# 2_EE-10_and_SIM_AFE_Interface.net
KiCad netlist of a schematic drawn in Altium Designer
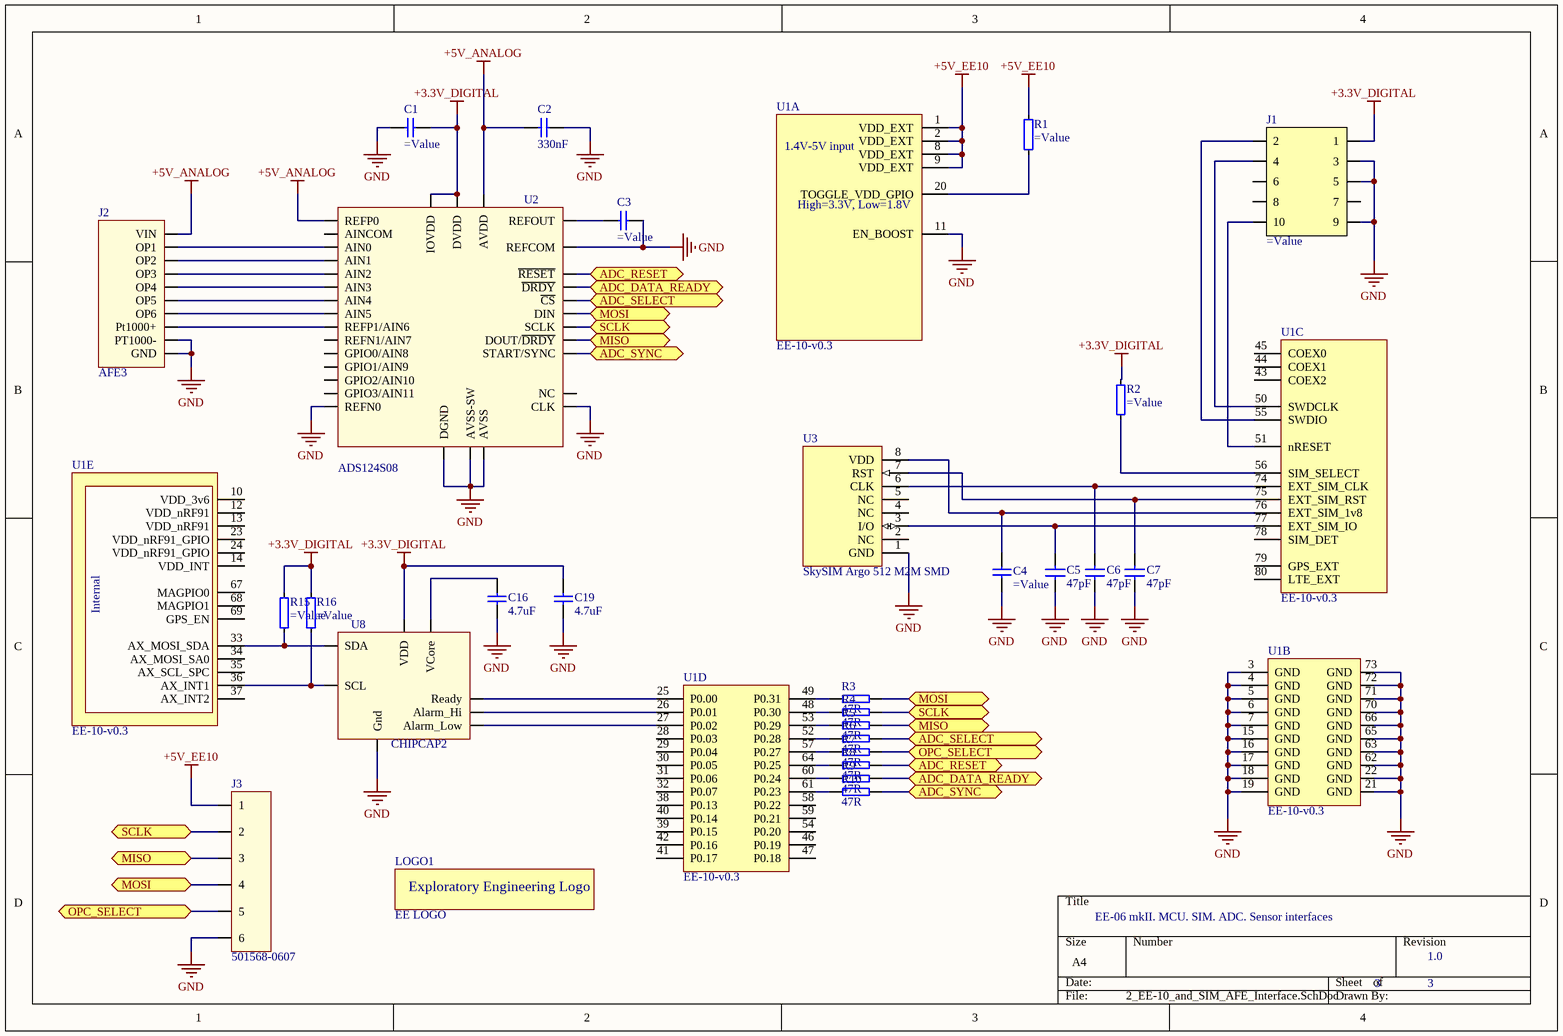
[diagram p0: 2_EE-10_and_SIM_AFE_Interface.SchDoc]

(export (version "E")
  (design (tool "Eeschema 10.0.6"))
  (components
    (comp (ref "C1")
      (value "~")
      (footprint "CAPC1005X04L")
      (description "CAP CER 100nF 16V X7R 0402")
      (fields
        (field (name "MANUFACTURER") "Murata Electronics North America")
        (field (name "MANUFACTURER PART NUMBER") "GRM155R71C104KA88D")
      )
      (libsource (lib "Skunkworks Library") (part "GRM155R71C104KA88D"))
    )
    (comp (ref "C2")
      (value "330nF")
      (footprint "CAPC1005X04L")
      (description "CAP CER 0.33UF 10V X5R 0402")
      (fields
        (field (name "MANUFACTURER") "Yageo")
        (field (name "MANUFACTURER PART NUMBER") "CC0402KRX5R6BB334")
      )
      (libsource (lib "Skunkworks Library") (part "CC0402KRX5R6BB334"))
    )
    (comp (ref "C3")
      (value "~")
      (footprint "CAPC1005X04L")
      (description "CAP CER 1UF 6.3V X7R 0402")
      (fields
        (field (name "MANUFACTURER") "Murata Electronics North America")
        (field (name "MANUFACTURER PART NUMBER") "GRM155R70J105KA12D")
      )
      (libsource (lib "Skunkworks Library") (part "GRM155R70J105KA12D"))
    )
    (comp (ref "C4")
      (value "~")
      (footprint "CAPC1005X04L")
      (description "CAP CER 100nF 16V X7R 0402")
      (fields
        (field (name "MANUFACTURER") "Murata Electronics North America")
        (field (name "MANUFACTURER PART NUMBER") "GRM155R71C104KA88D")
      )
      (libsource (lib "Skunkworks Library") (part "GRM155R71C104KA88D"))
    )
    (comp (ref "C5")
      (value "47pF")
      (footprint "CAPC1005X04L")
      (description "Multilayer Ceramic Capacitors MLCC - SMD/SMT 0402 47pF 50volts C0G 1%")
      (libsource (lib "Skunkworks Library") (part "GRM1555C1H470FA01D"))
    )
    (comp (ref "C6")
      (value "47pF")
      (footprint "CAPC1005X04L")
      (description "Multilayer Ceramic Capacitors MLCC - SMD/SMT 0402 47pF 50volts C0G 1%")
      (libsource (lib "Skunkworks Library") (part "GRM1555C1H470FA01D"))
    )
    (comp (ref "C7")
      (value "47pF")
      (footprint "CAPC1005X04L")
      (description "Multilayer Ceramic Capacitors MLCC - SMD/SMT 0402 47pF 50volts C0G 1%")
      (libsource (lib "Skunkworks Library") (part "GRM1555C1H470FA01D"))
    )
    (comp (ref "C16")
      (value "4.7uF")
      (footprint "CAPC1005X04L")
      (description "CAP CER 4.7UF 6.3V X5R 0402")
      (fields
        (field (name "MANUFACTURER") "Murata")
        (field (name "MANUFACTURER PART NUMBER") "GRM155R60J475ME47D")
      )
      (libsource (lib "Skunkworks Library") (part "GRM155R60J475ME47D"))
    )
    (comp (ref "C19")
      (value "4.7uF")
      (footprint "CAPC1005X04L")
      (description "CAP CER 4.7UF 6.3V X5R 0402")
      (fields
        (field (name "MANUFACTURER") "Murata")
        (field (name "MANUFACTURER PART NUMBER") "GRM155R60J475ME47D")
      )
      (libsource (lib "Skunkworks Library") (part "GRM155R60J475ME47D"))
    )
    (comp (ref "J1")
      (value "~")
      (footprint "FTSH-105-K")
      (description "CONN HEADER 10POS DUAL .05\" SMD")
      (fields
        (field (name "MANUFACTURER") "Samtec Inc.")
        (field (name "MANUFACTURER PART NUMBER") "FTSH-105-01-F-DV-K-P")
      )
      (libsource (lib "Skunkworks Library") (part "FTSH-105-01-F-DV-K-P"))
    )
    (comp (ref "J2")
      (value "AFE3")
      (footprint "AFE3_IDC_CABLE")
      (libsource (lib "Skunkworks Library") (part "AFE3"))
    )
    (comp (ref "J3")
      (value "501568-0607")
      (footprint "CONN 6 PIN PICOCLASP")
      (description "CONN HEADER SMD R/A 6POS 1MM")
      (fields (field (name "MANUFACTURER") "Molex"))
      (libsource (lib "Skunkworks Library") (part "501568-0607"))
    )
    (comp (ref "LOGO1")
      (value "EE LOGO")
      (footprint "EE_LOGO")
      (description "Exploratory Engineering Logo Silkscreen")
      (libsource (lib "Skunkworks Library") (part "EE-LOGO"))
    )
    (comp (ref "R1")
      (value "~")
      (footprint "RESC1005X04L")
      (description "RES SMD 10K OHM 1% 1/16W 0402")
      (fields
        (field (name "MANUFACTURER") "Yageo")
        (field (name "MANUFACTURER PART NUMBER") "RC0402FR-0710KL")
      )
      (libsource (lib "Skunkworks Library") (part "RC0402FR-0710KL"))
    )
    (comp (ref "R2")
      (value "~")
      (footprint "RESC1005X04L")
      (description "RES SMD 10K OHM 1% 1/16W 0402")
      (fields
        (field (name "MANUFACTURER") "Yageo")
        (field (name "MANUFACTURER PART NUMBER") "RC0402FR-0710KL")
      )
      (libsource (lib "Skunkworks Library") (part "RC0402FR-0710KL"))
    )
    (comp (ref "R3")
      (value "47R")
      (footprint "RESC1005X04L")
      (description "RES SMD 47 OHM 5% 1/16W 0402")
      (fields
        (field (name "MANUFACTURER") "Yageo")
        (field (name "MANUFACTURER PART NUMBER") "RC0402JR-0747RL")
      )
      (libsource (lib "Skunkworks Library") (part "RC0402JR-0747RL"))
    )
    (comp (ref "R4")
      (value "47R")
      (footprint "RESC1005X04L")
      (description "RES SMD 47 OHM 5% 1/16W 0402")
      (fields
        (field (name "MANUFACTURER") "Yageo")
        (field (name "MANUFACTURER PART NUMBER") "RC0402JR-0747RL")
      )
      (libsource (lib "Skunkworks Library") (part "RC0402JR-0747RL"))
    )
    (comp (ref "R5")
      (value "47R")
      (footprint "RESC1005X04L")
      (description "RES SMD 47 OHM 5% 1/16W 0402")
      (fields
        (field (name "MANUFACTURER") "Yageo")
        (field (name "MANUFACTURER PART NUMBER") "RC0402JR-0747RL")
      )
      (libsource (lib "Skunkworks Library") (part "RC0402JR-0747RL"))
    )
    (comp (ref "R6")
      (value "47R")
      (footprint "RESC1005X04L")
      (description "RES SMD 47 OHM 5% 1/16W 0402")
      (fields
        (field (name "MANUFACTURER") "Yageo")
        (field (name "MANUFACTURER PART NUMBER") "RC0402JR-0747RL")
      )
      (libsource (lib "Skunkworks Library") (part "RC0402JR-0747RL"))
    )
    (comp (ref "R7")
      (value "47R")
      (footprint "RESC1005X04L")
      (description "RES SMD 47 OHM 5% 1/16W 0402")
      (fields
        (field (name "MANUFACTURER") "Yageo")
        (field (name "MANUFACTURER PART NUMBER") "RC0402JR-0747RL")
      )
      (libsource (lib "Skunkworks Library") (part "RC0402JR-0747RL"))
    )
    (comp (ref "R8")
      (value "47R")
      (footprint "RESC1005X04L")
      (description "RES SMD 47 OHM 5% 1/16W 0402")
      (fields
        (field (name "MANUFACTURER") "Yageo")
        (field (name "MANUFACTURER PART NUMBER") "RC0402JR-0747RL")
      )
      (libsource (lib "Skunkworks Library") (part "RC0402JR-0747RL"))
    )
    (comp (ref "R9")
      (value "47R")
      (footprint "RESC1005X04L")
      (description "RES SMD 47 OHM 5% 1/16W 0402")
      (fields
        (field (name "MANUFACTURER") "Yageo")
        (field (name "MANUFACTURER PART NUMBER") "RC0402JR-0747RL")
      )
      (libsource (lib "Skunkworks Library") (part "RC0402JR-0747RL"))
    )
    (comp (ref "R10")
      (value "47R")
      (footprint "RESC1005X04L")
      (description "RES SMD 47 OHM 5% 1/16W 0402")
      (fields
        (field (name "MANUFACTURER") "Yageo")
        (field (name "MANUFACTURER PART NUMBER") "RC0402JR-0747RL")
      )
      (libsource (lib "Skunkworks Library") (part "RC0402JR-0747RL"))
    )
    (comp (ref "R15")
      (value "~")
      (footprint "RESC1005X04L")
      (description "RES SMD 10K OHM 1% 1/16W 0402")
      (fields
        (field (name "MANUFACTURER") "Yageo")
        (field (name "MANUFACTURER PART NUMBER") "RC0402FR-0710KL")
      )
      (libsource (lib "Skunkworks Library") (part "RC0402FR-0710KL"))
    )
    (comp (ref "R16")
      (value "~")
      (footprint "RESC1005X04L")
      (description "RES SMD 10K OHM 1% 1/16W 0402")
      (fields
        (field (name "MANUFACTURER") "Yageo")
        (field (name "MANUFACTURER PART NUMBER") "RC0402FR-0710KL")
      )
      (libsource (lib "Skunkworks Library") (part "RC0402FR-0710KL"))
    )
    (comp (ref "U1")
      (value "EE-10-v0.3")
      (footprint "EE-10_V0.3")
      (description "EE-10 v0.3 PCB Module")
      (fields (field (name "MANUFACTURER") "Telenor"))
      (libsource (lib "Skunkworks Library") (part "EE-10-v0.3"))
    )
    (comp (ref "U2")
      (value "ADS124S08")
      (footprint "PQFP-G32")
      (description "IC ADC 24BIT 8CH I2C 32-TQFP")
      (fields
        (field (name "MANUFACTURER") "Texas Instruments")
        (field (name "MANUFACTURER PART NUMBER") "ADS124S08IPBS")
      )
      (libsource (lib "Skunkworks Library") (part "ADS124S08IPBS"))
    )
    (comp (ref "U3")
      (value "SkySIM Argo 512 M2M SMD")
      (footprint "QFN127P500X600X90_HS-9N")
      (description "SkySIM® Argo 512 M2M SMD - LTE")
      (libsource (lib "Skunkworks Library") (part "SKYSIM-ARGO-LTE-MFF2"))
    )
    (comp (ref "U8")
      (value "CHIPCAP2")
      (footprint "SENSOR_CHIPCAP2")
      (description "SENSOR HUMI/TEMP 3.3V I2C 2% SMD")
      (fields (field (name "MANUFACTURER") "Amphenol") (field (name "MANUFACTURER PART NUMBER") "CC2A35"))
      (libsource (lib "Skunkworks Library") (part "CC2D23S"))
    )
  )
  (nets
    (net (code "1") (name "+3.3V_DIGITAL") (class "Default")
      (node (ref "C1") (pin "1") (pinfunction "1_1") (pintype "passive"))
      (node (ref "C19") (pin "2") (pinfunction "2_2") (pintype "passive"))
      (node (ref "J1") (pin "1") (pinfunction "1_1") (pintype "passive"))
      (node (ref "R15") (pin "2") (pinfunction "2_2") (pintype "passive"))
      (node (ref "R16") (pin "2") (pinfunction "2_2") (pintype "passive"))
      (node (ref "R2") (pin "2") (pinfunction "2_2") (pintype "passive"))
      (node (ref "U2") (pin "15") (pinfunction "IOVDD_15") (pintype "passive"))
      (node (ref "U2") (pin "16") (pinfunction "DVDD_16") (pintype "passive"))
      (node (ref "U8") (pin "3") (pinfunction "VDD_3") (pintype "passive"))
    )
    (net (code "2") (name "+5V_ANALOG") (class "Default")
      (node (ref "C2") (pin "1") (pinfunction "1_1") (pintype "passive"))
      (node (ref "J2") (pin "5") (pinfunction "VIN_5") (pintype "passive"))
      (node (ref "U2") (pin "26") (pinfunction "AVDD_26") (pintype "passive"))
      (node (ref "U2") (pin "30") (pinfunction "REFP0_30") (pintype "passive"))
    )
    (net (code "3") (name "+5V_EE10") (class "Default")
      (node (ref "J3") (pin "1") (pinfunction "1_1") (pintype "passive"))
      (node (ref "R1") (pin "2") (pinfunction "2_2") (pintype "passive"))
      (node (ref "U1") (pin "1") (pinfunction "VDD_EXT_1") (pintype "passive"))
      (node (ref "U1") (pin "2") (pinfunction "VDD_EXT_2") (pintype "passive"))
      (node (ref "U1") (pin "8") (pinfunction "VDD_EXT_8") (pintype "passive"))
      (node (ref "U1") (pin "9") (pinfunction "VDD_EXT_9") (pintype "passive"))
    )
    (net (code "4") (name "/ADC_DATA_READY") (class "Default")
      (node (ref "R9") (pin "2") (pintype "passive"))
      (node (ref "U2") (pin "13") (pinfunction "~{DRDY}_13") (pintype "passive"))
    )
    (net (code "5") (name "/ADC_RESET") (class "Default")
      (node (ref "R8") (pin "2") (pintype "passive"))
      (node (ref "U2") (pin "18") (pinfunction "~{RESET}_18") (pintype "passive"))
    )
    (net (code "6") (name "/ADC_SELECT") (class "Default")
      (node (ref "R6") (pin "2") (pintype "passive"))
      (node (ref "U2") (pin "9") (pinfunction "~{CS}_9") (pintype "passive"))
    )
    (net (code "7") (name "/ADC_SYNC") (class "Default")
      (node (ref "R10") (pin "2") (pintype "passive"))
      (node (ref "U2") (pin "8") (pinfunction "START/SYNC_8") (pintype "passive"))
    )
    (net (code "8") (name "/MISO") (class "Default")
      (node (ref "J3") (pin "3") (pinfunction "3_3") (pintype "passive"))
      (node (ref "R5") (pin "2") (pintype "passive"))
      (node (ref "U2") (pin "12") (pinfunction "DOUT/~{DRDY}_12") (pintype "passive"))
    )
    (net (code "9") (name "/MOSI") (class "Default")
      (node (ref "J3") (pin "4") (pinfunction "4_4") (pintype "passive"))
      (node (ref "R3") (pin "2") (pintype "passive"))
      (node (ref "U2") (pin "10") (pinfunction "DIN_10") (pintype "passive"))
    )
    (net (code "10") (name "/OPC_SELECT") (class "Default")
      (node (ref "J3") (pin "5") (pinfunction "5_5") (pintype "passive"))
      (node (ref "R7") (pin "2") (pintype "passive"))
    )
    (net (code "11") (name "/SCLK") (class "Default")
      (node (ref "J3") (pin "2") (pinfunction "2_2") (pintype "passive"))
      (node (ref "R4") (pin "2") (pintype "passive"))
      (node (ref "U2") (pin "11") (pinfunction "SCLK_11") (pintype "passive"))
    )
    (net (code "12") (name "GND") (class "Default")
      (node (ref "C1") (pin "2") (pinfunction "2_2") (pintype "passive"))
      (node (ref "C16") (pin "1") (pinfunction "1_1") (pintype "passive"))
      (node (ref "C19") (pin "1") (pinfunction "1_1") (pintype "passive"))
      (node (ref "C2") (pin "2") (pinfunction "2_2") (pintype "passive"))
      (node (ref "C3") (pin "2") (pinfunction "2_2") (pintype "passive"))
      (node (ref "C4") (pin "1") (pinfunction "1_1") (pintype "passive"))
      (node (ref "C5") (pin "2") (pintype "passive"))
      (node (ref "C6") (pin "2") (pintype "passive"))
      (node (ref "C7") (pin "2") (pintype "passive"))
      (node (ref "J1") (pin "3") (pinfunction "3_3") (pintype "passive"))
      (node (ref "J1") (pin "5") (pinfunction "5_5") (pintype "passive"))
      (node (ref "J1") (pin "9") (pinfunction "9_9") (pintype "passive"))
      (node (ref "J2") (pin "10") (pinfunction "PT1000-_10") (pintype "passive"))
      (node (ref "J2") (pin "6") (pinfunction "GND_6") (pintype "passive"))
      (node (ref "J3") (pin "6") (pinfunction "6_6") (pintype "passive"))
      (node (ref "U1") (pin "11") (pinfunction "EN_BOOST_11") (pintype "passive"))
      (node (ref "U1") (pin "15") (pinfunction "GND_15") (pintype "passive"))
      (node (ref "U1") (pin "16") (pinfunction "GND_16") (pintype "passive"))
      (node (ref "U1") (pin "17") (pinfunction "GND_17") (pintype "passive"))
      (node (ref "U1") (pin "18") (pinfunction "GND_18") (pintype "passive"))
      (node (ref "U1") (pin "19") (pinfunction "GND_19") (pintype "passive"))
      (node (ref "U1") (pin "21") (pinfunction "GND_21") (pintype "passive"))
      (node (ref "U1") (pin "22") (pinfunction "GND_22") (pintype "passive"))
      (node (ref "U1") (pin "3") (pinfunction "GND_3") (pintype "passive"))
      (node (ref "U1") (pin "4") (pinfunction "GND_4") (pintype "passive"))
      (node (ref "U1") (pin "5") (pinfunction "GND_5") (pintype "passive"))
      (node (ref "U1") (pin "6") (pinfunction "GND_6") (pintype "passive"))
      (node (ref "U1") (pin "62") (pinfunction "GND_62") (pintype "passive"))
      (node (ref "U1") (pin "63") (pinfunction "GND_63") (pintype "passive"))
      (node (ref "U1") (pin "65") (pinfunction "GND_65") (pintype "passive"))
      (node (ref "U1") (pin "66") (pinfunction "GND_66") (pintype "passive"))
      (node (ref "U1") (pin "7") (pinfunction "GND_7") (pintype "passive"))
      (node (ref "U1") (pin "70") (pinfunction "GND_70") (pintype "passive"))
      (node (ref "U1") (pin "71") (pinfunction "GND_71") (pintype "passive"))
      (node (ref "U1") (pin "72") (pinfunction "GND_72") (pintype "passive"))
      (node (ref "U1") (pin "73") (pinfunction "GND_73") (pintype "passive"))
      (node (ref "U2") (pin "14") (pinfunction "DGND_14") (pintype "passive"))
      (node (ref "U2") (pin "17") (pinfunction "CLK_17") (pintype "passive"))
      (node (ref "U2") (pin "24") (pinfunction "REFCOM_24") (pintype "passive"))
      (node (ref "U2") (pin "27") (pinfunction "AVSS_27") (pintype "passive"))
      (node (ref "U2") (pin "28") (pinfunction "AVSS-SW_28") (pintype "passive"))
      (node (ref "U2") (pin "29") (pinfunction "REFN0_29") (pintype "passive"))
      (node (ref "U3") (pin "1") (pinfunction "GND_1") (pintype "passive"))
      (node (ref "U8") (pin "2") (pinfunction "Gnd_2") (pintype "passive"))
    )
    (net (code "13") (name "Net-(J2-OP1)") (class "Default")
      (node (ref "J2") (pin "9") (pinfunction "OP1_9") (pintype "passive"))
      (node (ref "U2") (pin "7") (pinfunction "AIN0_7") (pintype "passive"))
    )
    (net (code "14") (name "Net-(J2-OP2)") (class "Default")
      (node (ref "J2") (pin "2") (pinfunction "OP2_2") (pintype "passive"))
      (node (ref "U2") (pin "6") (pinfunction "AIN1_6") (pintype "passive"))
    )
    (net (code "15") (name "Net-(J2-OP3)") (class "Default")
      (node (ref "J2") (pin "8") (pinfunction "OP3_8") (pintype "passive"))
      (node (ref "U2") (pin "5") (pinfunction "AIN2_5") (pintype "passive"))
    )
    (net (code "16") (name "Net-(J2-OP4)") (class "Default")
      (node (ref "J2") (pin "3") (pinfunction "OP4_3") (pintype "passive"))
      (node (ref "U2") (pin "4") (pinfunction "AIN3_4") (pintype "passive"))
    )
    (net (code "17") (name "Net-(J2-OP5)") (class "Default")
      (node (ref "J2") (pin "7") (pinfunction "OP5_7") (pintype "passive"))
      (node (ref "U2") (pin "3") (pinfunction "AIN4_3") (pintype "passive"))
    )
    (net (code "18") (name "Net-(J2-OP6)") (class "Default")
      (node (ref "J2") (pin "4") (pinfunction "OP6_4") (pintype "passive"))
      (node (ref "U2") (pin "2") (pinfunction "AIN5_2") (pintype "passive"))
    )
    (net (code "19") (name "Net-(J2-Pt1000+)") (class "Default")
      (node (ref "J2") (pin "1") (pinfunction "Pt1000+_1") (pintype "passive"))
      (node (ref "U2") (pin "32") (pinfunction "REFP1/AIN6_32") (pintype "passive"))
    )
    (net (code "20") (name "Net-(U1A-TOGGLE_VDD_GPIO)") (class "Default")
      (node (ref "R1") (pin "1") (pinfunction "1_1") (pintype "passive"))
      (node (ref "U1") (pin "20") (pinfunction "TOGGLE_VDD_GPIO_20") (pintype "passive"))
    )
    (net (code "21") (name "Net-(U1C-EXT_SIM_1v8)") (class "Default")
      (node (ref "C4") (pin "2") (pinfunction "2_2") (pintype "passive"))
      (node (ref "U1") (pin "76") (pinfunction "EXT_SIM_1v8_76") (pintype "passive"))
      (node (ref "U3") (pin "8") (pinfunction "VDD_8") (pintype "passive"))
    )
    (net (code "22") (name "Net-(U1C-EXT_SIM_CLK)") (class "Default")
      (node (ref "C6") (pin "1") (pintype "passive"))
      (node (ref "U1") (pin "74") (pinfunction "EXT_SIM_CLK_74") (pintype "passive"))
      (node (ref "U3") (pin "6") (pinfunction "CLK_6") (pintype "passive"))
    )
    (net (code "23") (name "Net-(U1C-EXT_SIM_IO)") (class "Default")
      (node (ref "C5") (pin "1") (pintype "passive"))
      (node (ref "U1") (pin "77") (pinfunction "EXT_SIM_IO_77") (pintype "passive"))
      (node (ref "U3") (pin "3") (pinfunction "I/O_3") (pintype "bidirectional"))
    )
    (net (code "24") (name "Net-(U1C-EXT_SIM_RST)") (class "Default")
      (node (ref "C7") (pin "1") (pintype "passive"))
      (node (ref "U1") (pin "75") (pinfunction "EXT_SIM_RST_75") (pintype "passive"))
      (node (ref "U3") (pin "7") (pinfunction "RST_7") (pintype "input"))
    )
    (net (code "25") (name "Net-(U1C-SIM_SELECT)") (class "Default")
      (node (ref "R2") (pin "1") (pinfunction "1_1") (pintype "passive"))
      (node (ref "U1") (pin "56") (pinfunction "SIM_SELECT_56") (pintype "passive"))
    )
    (net (code "26") (name "Net-(U1C-SWDCLK)") (class "Default")
      (node (ref "J1") (pin "4") (pinfunction "4_4") (pintype "passive"))
      (node (ref "U1") (pin "50") (pinfunction "SWDCLK_50") (pintype "passive"))
    )
    (net (code "27") (name "Net-(U1C-SWDIO)") (class "Default")
      (node (ref "J1") (pin "2") (pinfunction "2_2") (pintype "passive"))
      (node (ref "U1") (pin "55") (pinfunction "SWDIO_55") (pintype "passive"))
    )
    (net (code "28") (name "Net-(U1C-nRESET)") (class "Default")
      (node (ref "J1") (pin "10") (pinfunction "10_10") (pintype "passive"))
      (node (ref "U1") (pin "51") (pinfunction "nRESET_51") (pintype "passive"))
    )
    (net (code "29") (name "Net-(U1D-P0.00)") (class "Default")
      (node (ref "U1") (pin "25") (pinfunction "P0.00_25") (pintype "passive"))
      (node (ref "U8") (pin "6") (pinfunction "Ready_6") (pintype "passive"))
    )
    (net (code "30") (name "Net-(U1D-P0.01)") (class "Default")
      (node (ref "U1") (pin "26") (pinfunction "P0.01_26") (pintype "passive"))
      (node (ref "U8") (pin "4") (pinfunction "Alarm_Hi_4") (pintype "passive"))
    )
    (net (code "31") (name "Net-(U1D-P0.02)") (class "Default")
      (node (ref "U1") (pin "27") (pinfunction "P0.02_27") (pintype "passive"))
      (node (ref "U8") (pin "5") (pinfunction "Alarm_Low_5") (pintype "passive"))
    )
    (net (code "32") (name "Net-(U1D-P0.23)") (class "Default")
      (node (ref "R10") (pin "1") (pintype "passive"))
      (node (ref "U1") (pin "61") (pinfunction "P0.23_61") (pintype "passive"))
    )
    (net (code "33") (name "Net-(U1D-P0.24)") (class "Default")
      (node (ref "R9") (pin "1") (pintype "passive"))
      (node (ref "U1") (pin "60") (pinfunction "P0.24_60") (pintype "passive"))
    )
    (net (code "34") (name "Net-(U1D-P0.25)") (class "Default")
      (node (ref "R8") (pin "1") (pintype "passive"))
      (node (ref "U1") (pin "64") (pinfunction "P0.25_64") (pintype "passive"))
    )
    (net (code "35") (name "Net-(U1D-P0.27)") (class "Default")
      (node (ref "R7") (pin "1") (pintype "passive"))
      (node (ref "U1") (pin "57") (pinfunction "P0.27_57") (pintype "passive"))
    )
    (net (code "36") (name "Net-(U1D-P0.28)") (class "Default")
      (node (ref "R6") (pin "1") (pintype "passive"))
      (node (ref "U1") (pin "52") (pinfunction "P0.28_52") (pintype "passive"))
    )
    (net (code "37") (name "Net-(U1D-P0.29)") (class "Default")
      (node (ref "R5") (pin "1") (pintype "passive"))
      (node (ref "U1") (pin "53") (pinfunction "P0.29_53") (pintype "passive"))
    )
    (net (code "38") (name "Net-(U1D-P0.30)") (class "Default")
      (node (ref "R4") (pin "1") (pintype "passive"))
      (node (ref "U1") (pin "48") (pinfunction "P0.30_48") (pintype "passive"))
    )
    (net (code "39") (name "Net-(U1D-P0.31)") (class "Default")
      (node (ref "R3") (pin "1") (pintype "passive"))
      (node (ref "U1") (pin "49") (pinfunction "P0.31_49") (pintype "passive"))
    )
    (net (code "40") (name "Net-(U1E-AX_INT1)") (class "Default")
      (node (ref "R16") (pin "1") (pinfunction "1_1") (pintype "passive"))
      (node (ref "U1") (pin "36") (pinfunction "AX_INT1_36") (pintype "passive"))
      (node (ref "U8") (pin "8") (pinfunction "SCL_8") (pintype "passive"))
    )
    (net (code "41") (name "Net-(U1E-AX_MOSI_SDA)") (class "Default")
      (node (ref "R15") (pin "1") (pinfunction "1_1") (pintype "passive"))
      (node (ref "U1") (pin "33") (pinfunction "AX_MOSI_SDA_33") (pintype "passive"))
      (node (ref "U8") (pin "7") (pinfunction "SDA_7") (pintype "passive"))
    )
    (net (code "42") (name "Net-(U2-REFOUT)") (class "Default")
      (node (ref "C3") (pin "1") (pinfunction "1_1") (pintype "passive"))
      (node (ref "U2") (pin "23") (pinfunction "REFOUT_23") (pintype "passive"))
    )
    (net (code "43") (name "Net-(U8-VCore)") (class "Default")
      (node (ref "C16") (pin "2") (pinfunction "2_2") (pintype "passive"))
      (node (ref "U8") (pin "1") (pinfunction "VCore_1") (pintype "passive"))
    )
    (net (code "44") (name "unconnected-(J1-Pad6)") (class "Default")
      (node (ref "J1") (pin "6") (pinfunction "6_6") (pintype "passive"))
    )
    (net (code "45") (name "unconnected-(J1-Pad7)") (class "Default")
      (node (ref "J1") (pin "7") (pinfunction "7_7") (pintype "passive"))
    )
    (net (code "46") (name "unconnected-(J1-Pad8)") (class "Default")
      (node (ref "J1") (pin "8") (pinfunction "8_8") (pintype "passive"))
    )
    (net (code "47") (name "unconnected-(U1C-COEX0-Pad45)") (class "Default")
      (node (ref "U1") (pin "45") (pinfunction "COEX0_45") (pintype "passive"))
    )
    (net (code "48") (name "unconnected-(U1C-COEX1-Pad44)") (class "Default")
      (node (ref "U1") (pin "44") (pinfunction "COEX1_44") (pintype "passive"))
    )
    (net (code "49") (name "unconnected-(U1C-COEX2-Pad43)") (class "Default")
      (node (ref "U1") (pin "43") (pinfunction "COEX2_43") (pintype "passive"))
    )
    (net (code "50") (name "unconnected-(U1C-GPS_EXT-Pad79)") (class "Default")
      (node (ref "U1") (pin "79") (pinfunction "GPS_EXT_79") (pintype "passive"))
    )
    (net (code "51") (name "unconnected-(U1C-LTE_EXT-Pad80)") (class "Default")
      (node (ref "U1") (pin "80") (pinfunction "LTE_EXT_80") (pintype "passive"))
    )
    (net (code "52") (name "unconnected-(U1C-SIM_DET-Pad78)") (class "Default")
      (node (ref "U1") (pin "78") (pinfunction "SIM_DET_78") (pintype "passive"))
    )
    (net (code "53") (name "unconnected-(U1D-P0.03-Pad28)") (class "Default")
      (node (ref "U1") (pin "28") (pinfunction "P0.03_28") (pintype "passive"))
    )
    (net (code "54") (name "unconnected-(U1D-P0.04-Pad29)") (class "Default")
      (node (ref "U1") (pin "29") (pinfunction "P0.04_29") (pintype "passive"))
    )
    (net (code "55") (name "unconnected-(U1D-P0.05-Pad30)") (class "Default")
      (node (ref "U1") (pin "30") (pinfunction "P0.05_30") (pintype "passive"))
    )
    (net (code "56") (name "unconnected-(U1D-P0.06-Pad31)") (class "Default")
      (node (ref "U1") (pin "31") (pinfunction "P0.06_31") (pintype "passive"))
    )
    (net (code "57") (name "unconnected-(U1D-P0.07-Pad32)") (class "Default")
      (node (ref "U1") (pin "32") (pinfunction "P0.07_32") (pintype "passive"))
    )
    (net (code "58") (name "unconnected-(U1D-P0.13-Pad38)") (class "Default")
      (node (ref "U1") (pin "38") (pinfunction "P0.13_38") (pintype "passive"))
    )
    (net (code "59") (name "unconnected-(U1D-P0.14-Pad40)") (class "Default")
      (node (ref "U1") (pin "40") (pinfunction "P0.14_40") (pintype "passive"))
    )
    (net (code "60") (name "unconnected-(U1D-P0.15-Pad39)") (class "Default")
      (node (ref "U1") (pin "39") (pinfunction "P0.15_39") (pintype "passive"))
    )
    (net (code "61") (name "unconnected-(U1D-P0.16-Pad42)") (class "Default")
      (node (ref "U1") (pin "42") (pinfunction "P0.16_42") (pintype "passive"))
    )
    (net (code "62") (name "unconnected-(U1D-P0.17-Pad41)") (class "Default")
      (node (ref "U1") (pin "41") (pinfunction "P0.17_41") (pintype "passive"))
    )
    (net (code "63") (name "unconnected-(U1D-P0.18-Pad47)") (class "Default")
      (node (ref "U1") (pin "47") (pinfunction "P0.18_47") (pintype "passive"))
    )
    (net (code "64") (name "unconnected-(U1D-P0.19-Pad46)") (class "Default")
      (node (ref "U1") (pin "46") (pinfunction "P0.19_46") (pintype "passive"))
    )
    (net (code "65") (name "unconnected-(U1D-P0.20-Pad54)") (class "Default")
      (node (ref "U1") (pin "54") (pinfunction "P0.20_54") (pintype "passive"))
    )
    (net (code "66") (name "unconnected-(U1D-P0.21-Pad59)") (class "Default")
      (node (ref "U1") (pin "59") (pinfunction "P0.21_59") (pintype "passive"))
    )
    (net (code "67") (name "unconnected-(U1D-P0.22-Pad58)") (class "Default")
      (node (ref "U1") (pin "58") (pinfunction "P0.22_58") (pintype "passive"))
    )
    (net (code "68") (name "unconnected-(U1E-AX_INT2-Pad37)") (class "Default")
      (node (ref "U1") (pin "37") (pinfunction "AX_INT2_37") (pintype "passive"))
    )
    (net (code "69") (name "unconnected-(U1E-AX_MOSI_SA0-Pad34)") (class "Default")
      (node (ref "U1") (pin "34") (pinfunction "AX_MOSI_SA0_34") (pintype "passive"))
    )
    (net (code "70") (name "unconnected-(U1E-AX_SCL_SPC-Pad35)") (class "Default")
      (node (ref "U1") (pin "35") (pinfunction "AX_SCL_SPC_35") (pintype "passive"))
    )
    (net (code "71") (name "unconnected-(U1E-GPS_EN-Pad69)") (class "Default")
      (node (ref "U1") (pin "69") (pinfunction "GPS_EN_69") (pintype "passive"))
    )
    (net (code "72") (name "unconnected-(U1E-MAGPIO0-Pad67)") (class "Default")
      (node (ref "U1") (pin "67") (pinfunction "MAGPIO0_67") (pintype "passive"))
    )
    (net (code "73") (name "unconnected-(U1E-MAGPIO1-Pad68)") (class "Default")
      (node (ref "U1") (pin "68") (pinfunction "MAGPIO1_68") (pintype "passive"))
    )
    (net (code "74") (name "unconnected-(U1E-VDD_3v6-Pad10)") (class "Default")
      (node (ref "U1") (pin "10") (pinfunction "VDD_3v6_10") (pintype "passive"))
    )
    (net (code "75") (name "unconnected-(U1E-VDD_INT-Pad14)") (class "Default")
      (node (ref "U1") (pin "14") (pinfunction "VDD_INT_14") (pintype "passive"))
    )
    (net (code "76") (name "unconnected-(U1E-VDD_nRF91-Pad12)") (class "Default")
      (node (ref "U1") (pin "12") (pinfunction "VDD_nRF91_12") (pintype "passive"))
    )
    (net (code "77") (name "unconnected-(U1E-VDD_nRF91-Pad13)") (class "Default")
      (node (ref "U1") (pin "13") (pinfunction "VDD_nRF91_13") (pintype "passive"))
    )
    (net (code "78") (name "unconnected-(U1E-VDD_nRF91_GPIO-Pad23)") (class "Default")
      (node (ref "U1") (pin "23") (pinfunction "VDD_nRF91_GPIO_23") (pintype "passive"))
    )
    (net (code "79") (name "unconnected-(U1E-VDD_nRF91_GPIO-Pad24)") (class "Default")
      (node (ref "U1") (pin "24") (pinfunction "VDD_nRF91_GPIO_24") (pintype "passive"))
    )
    (net (code "80") (name "unconnected-(U2-AINCOM-Pad1)") (class "Default")
      (node (ref "U2") (pin "1") (pinfunction "AINCOM_1") (pintype "passive"))
    )
    (net (code "81") (name "unconnected-(U2-GPIO0{slash}AIN8-Pad22)") (class "Default")
      (node (ref "U2") (pin "22") (pinfunction "GPIO0/AIN8_22") (pintype "passive"))
    )
    (net (code "82") (name "unconnected-(U2-GPIO1{slash}AIN9-Pad21)") (class "Default")
      (node (ref "U2") (pin "21") (pinfunction "GPIO1/AIN9_21") (pintype "passive"))
    )
    (net (code "83") (name "unconnected-(U2-GPIO2{slash}AIN10-Pad20)") (class "Default")
      (node (ref "U2") (pin "20") (pinfunction "GPIO2/AIN10_20") (pintype "passive"))
    )
    (net (code "84") (name "unconnected-(U2-GPIO3{slash}AIN11-Pad19)") (class "Default")
      (node (ref "U2") (pin "19") (pinfunction "GPIO3/AIN11_19") (pintype "passive"))
    )
    (net (code "85") (name "unconnected-(U2-NC-Pad25)") (class "Default")
      (node (ref "U2") (pin "25") (pinfunction "NC_25") (pintype "passive"))
    )
    (net (code "86") (name "unconnected-(U2-REFN1{slash}AIN7-Pad31)") (class "Default")
      (node (ref "U2") (pin "31") (pinfunction "REFN1/AIN7_31") (pintype "passive"))
    )
    (net (code "87") (name "unconnected-(U3-NC-Pad2)") (class "Default")
      (node (ref "U3") (pin "2") (pinfunction "NC_2") (pintype "passive"))
    )
    (net (code "88") (name "unconnected-(U3-NC-Pad4)") (class "Default")
      (node (ref "U3") (pin "4") (pinfunction "NC_4") (pintype "passive"))
    )
    (net (code "89") (name "unconnected-(U3-NC-Pad5)") (class "Default")
      (node (ref "U3") (pin "5") (pinfunction "NC_5") (pintype "passive"))
    )
  )
)
